# Sheet3.net
KiCad netlist of a schematic drawn in Altium Designer
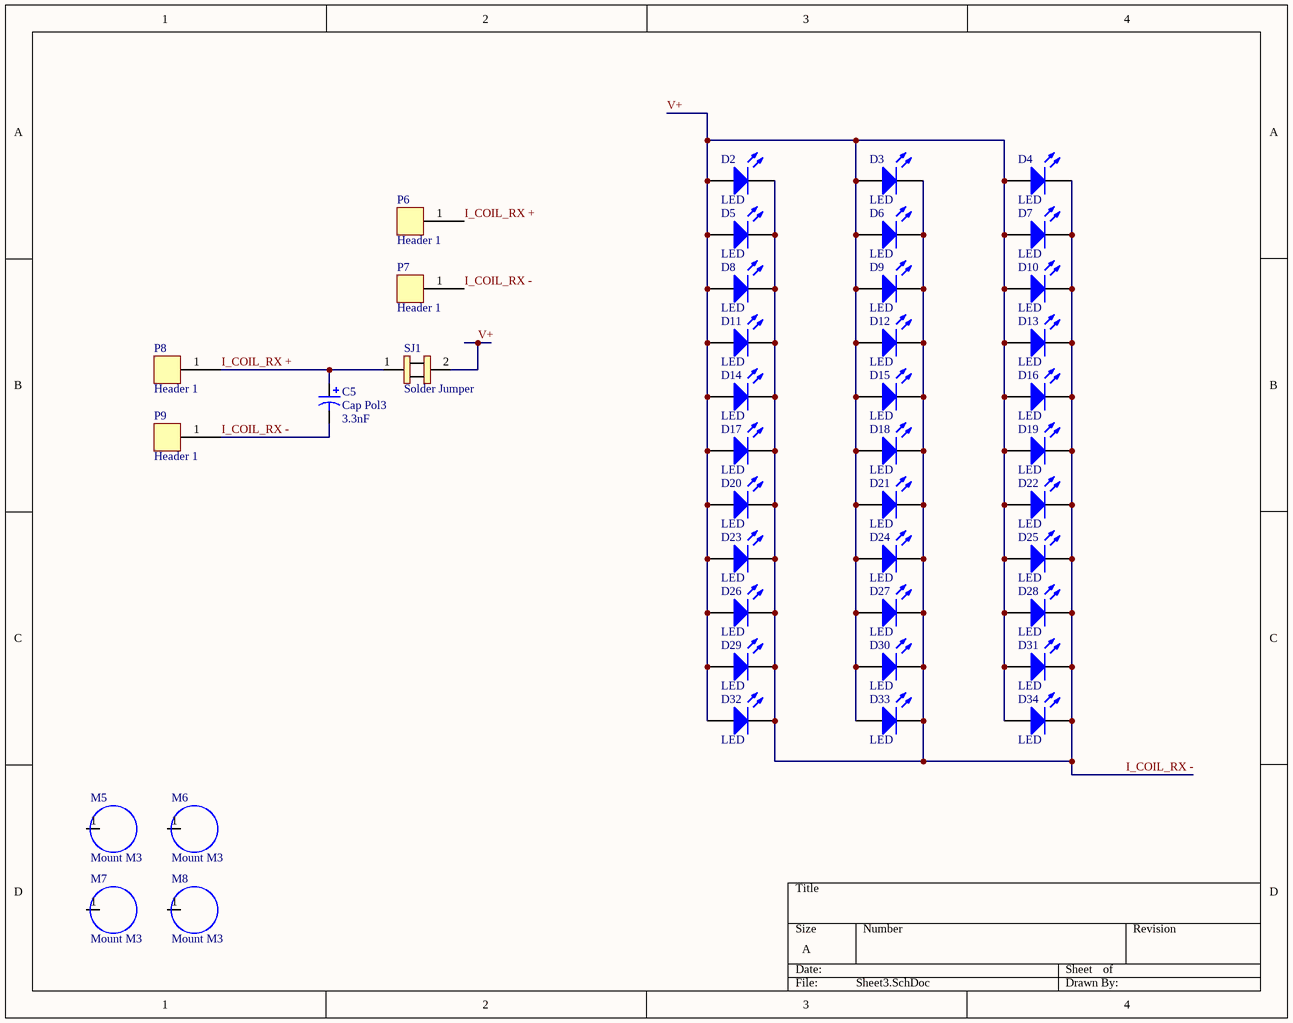
[diagram p0: Sheet3.SchDoc]

(export (version "E")
  (design (tool "Eeschema 10.0.6"))
  (components
    (comp (ref "C5")
      (value "Cap Pol3")
      (footprint "C0805")
      (description "Polarized Capacitor (Surface Mount)")
      (fields (field (name "ALTIUM_VALUE") "3.3nF") (field (name "PUBLISHER") "Altium Limited"))
      (libsource (lib "Miscellaneous Devices") (part "Cap Pol3"))
    )
    (comp (ref "D2")
      (value "LED")
      (footprint "0805")
      (description "Typical RED GaAs LED")
      (fields (field (name "PUBLISHER") "Altium Limited"))
      (libsource (lib "Miscellaneous Devices") (part "LED1"))
    )
    (comp (ref "D3")
      (value "LED")
      (footprint "0805")
      (description "Typical RED GaAs LED")
      (fields (field (name "PUBLISHER") "Altium Limited"))
      (libsource (lib "Miscellaneous Devices") (part "LED1"))
    )
    (comp (ref "D4")
      (value "LED")
      (footprint "0805")
      (description "Typical RED GaAs LED")
      (fields (field (name "PUBLISHER") "Altium Limited"))
      (libsource (lib "Miscellaneous Devices") (part "LED1"))
    )
    (comp (ref "D5")
      (value "LED")
      (footprint "0805")
      (description "Typical RED GaAs LED")
      (fields (field (name "PUBLISHER") "Altium Limited"))
      (libsource (lib "Miscellaneous Devices") (part "LED1"))
    )
    (comp (ref "D6")
      (value "LED")
      (footprint "0805")
      (description "Typical RED GaAs LED")
      (fields (field (name "PUBLISHER") "Altium Limited"))
      (libsource (lib "Miscellaneous Devices") (part "LED1"))
    )
    (comp (ref "D7")
      (value "LED")
      (footprint "0805")
      (description "Typical RED GaAs LED")
      (fields (field (name "PUBLISHER") "Altium Limited"))
      (libsource (lib "Miscellaneous Devices") (part "LED1"))
    )
    (comp (ref "D8")
      (value "LED")
      (footprint "0805")
      (description "Typical RED GaAs LED")
      (fields (field (name "PUBLISHER") "Altium Limited"))
      (libsource (lib "Miscellaneous Devices") (part "LED1"))
    )
    (comp (ref "D9")
      (value "LED")
      (footprint "0805")
      (description "Typical RED GaAs LED")
      (fields (field (name "PUBLISHER") "Altium Limited"))
      (libsource (lib "Miscellaneous Devices") (part "LED1"))
    )
    (comp (ref "D10")
      (value "LED")
      (footprint "0805")
      (description "Typical RED GaAs LED")
      (fields (field (name "PUBLISHER") "Altium Limited"))
      (libsource (lib "Miscellaneous Devices") (part "LED1"))
    )
    (comp (ref "D11")
      (value "LED")
      (footprint "0805")
      (description "Typical RED GaAs LED")
      (fields (field (name "PUBLISHER") "Altium Limited"))
      (libsource (lib "Miscellaneous Devices") (part "LED1"))
    )
    (comp (ref "D12")
      (value "LED")
      (footprint "0805")
      (description "Typical RED GaAs LED")
      (fields (field (name "PUBLISHER") "Altium Limited"))
      (libsource (lib "Miscellaneous Devices") (part "LED1"))
    )
    (comp (ref "D13")
      (value "LED")
      (footprint "0805")
      (description "Typical RED GaAs LED")
      (fields (field (name "PUBLISHER") "Altium Limited"))
      (libsource (lib "Miscellaneous Devices") (part "LED1"))
    )
    (comp (ref "D14")
      (value "LED")
      (footprint "0805")
      (description "Typical RED GaAs LED")
      (fields (field (name "PUBLISHER") "Altium Limited"))
      (libsource (lib "Miscellaneous Devices") (part "LED1"))
    )
    (comp (ref "D15")
      (value "LED")
      (footprint "0805")
      (description "Typical RED GaAs LED")
      (fields (field (name "PUBLISHER") "Altium Limited"))
      (libsource (lib "Miscellaneous Devices") (part "LED1"))
    )
    (comp (ref "D16")
      (value "LED")
      (footprint "0805")
      (description "Typical RED GaAs LED")
      (fields (field (name "PUBLISHER") "Altium Limited"))
      (libsource (lib "Miscellaneous Devices") (part "LED1"))
    )
    (comp (ref "D17")
      (value "LED")
      (footprint "0805")
      (description "Typical RED GaAs LED")
      (fields (field (name "PUBLISHER") "Altium Limited"))
      (libsource (lib "Miscellaneous Devices") (part "LED1"))
    )
    (comp (ref "D18")
      (value "LED")
      (footprint "0805")
      (description "Typical RED GaAs LED")
      (fields (field (name "PUBLISHER") "Altium Limited"))
      (libsource (lib "Miscellaneous Devices") (part "LED1"))
    )
    (comp (ref "D19")
      (value "LED")
      (footprint "0805")
      (description "Typical RED GaAs LED")
      (fields (field (name "PUBLISHER") "Altium Limited"))
      (libsource (lib "Miscellaneous Devices") (part "LED1"))
    )
    (comp (ref "D20")
      (value "LED")
      (footprint "0805")
      (description "Typical RED GaAs LED")
      (fields (field (name "PUBLISHER") "Altium Limited"))
      (libsource (lib "Miscellaneous Devices") (part "LED1"))
    )
    (comp (ref "D21")
      (value "LED")
      (footprint "0805")
      (description "Typical RED GaAs LED")
      (fields (field (name "PUBLISHER") "Altium Limited"))
      (libsource (lib "Miscellaneous Devices") (part "LED1"))
    )
    (comp (ref "D22")
      (value "LED")
      (footprint "0805")
      (description "Typical RED GaAs LED")
      (fields (field (name "PUBLISHER") "Altium Limited"))
      (libsource (lib "Miscellaneous Devices") (part "LED1"))
    )
    (comp (ref "D23")
      (value "LED")
      (footprint "0805")
      (description "Typical RED GaAs LED")
      (fields (field (name "PUBLISHER") "Altium Limited"))
      (libsource (lib "Miscellaneous Devices") (part "LED1"))
    )
    (comp (ref "D24")
      (value "LED")
      (footprint "0805")
      (description "Typical RED GaAs LED")
      (fields (field (name "PUBLISHER") "Altium Limited"))
      (libsource (lib "Miscellaneous Devices") (part "LED1"))
    )
    (comp (ref "D25")
      (value "LED")
      (footprint "0805")
      (description "Typical RED GaAs LED")
      (fields (field (name "PUBLISHER") "Altium Limited"))
      (libsource (lib "Miscellaneous Devices") (part "LED1"))
    )
    (comp (ref "D26")
      (value "LED")
      (footprint "0805")
      (description "Typical RED GaAs LED")
      (fields (field (name "PUBLISHER") "Altium Limited"))
      (libsource (lib "Miscellaneous Devices") (part "LED1"))
    )
    (comp (ref "D27")
      (value "LED")
      (footprint "0805")
      (description "Typical RED GaAs LED")
      (fields (field (name "PUBLISHER") "Altium Limited"))
      (libsource (lib "Miscellaneous Devices") (part "LED1"))
    )
    (comp (ref "D28")
      (value "LED")
      (footprint "0805")
      (description "Typical RED GaAs LED")
      (fields (field (name "PUBLISHER") "Altium Limited"))
      (libsource (lib "Miscellaneous Devices") (part "LED1"))
    )
    (comp (ref "D29")
      (value "LED")
      (footprint "0805")
      (description "Typical RED GaAs LED")
      (fields (field (name "PUBLISHER") "Altium Limited"))
      (libsource (lib "Miscellaneous Devices") (part "LED1"))
    )
    (comp (ref "D30")
      (value "LED")
      (footprint "0805")
      (description "Typical RED GaAs LED")
      (fields (field (name "PUBLISHER") "Altium Limited"))
      (libsource (lib "Miscellaneous Devices") (part "LED1"))
    )
    (comp (ref "D31")
      (value "LED")
      (footprint "0805")
      (description "Typical RED GaAs LED")
      (fields (field (name "PUBLISHER") "Altium Limited"))
      (libsource (lib "Miscellaneous Devices") (part "LED1"))
    )
    (comp (ref "D32")
      (value "LED")
      (footprint "0805")
      (description "Typical RED GaAs LED")
      (fields (field (name "PUBLISHER") "Altium Limited"))
      (libsource (lib "Miscellaneous Devices") (part "LED1"))
    )
    (comp (ref "D33")
      (value "LED")
      (footprint "0805")
      (description "Typical RED GaAs LED")
      (fields (field (name "PUBLISHER") "Altium Limited"))
      (libsource (lib "Miscellaneous Devices") (part "LED1"))
    )
    (comp (ref "D34")
      (value "LED")
      (footprint "0805")
      (description "Typical RED GaAs LED")
      (fields (field (name "PUBLISHER") "Altium Limited"))
      (libsource (lib "Miscellaneous Devices") (part "LED1"))
    )
    (comp (ref "M5") (value "Mount M3") (libsource (lib "u104Systems") (part "Mount M3")))
    (comp (ref "M6") (value "Mount M3") (libsource (lib "u104Systems") (part "Mount M3")))
    (comp (ref "M7") (value "Mount M3") (libsource (lib "u104Systems") (part "Mount M3")))
    (comp (ref "M8") (value "Mount M3") (libsource (lib "u104Systems") (part "Mount M3")))
    (comp (ref "P6") (value "Header 1") (footprint "Pad") (libsource (lib "u104Systems") (part "Header 1")))
    (comp (ref "P7") (value "Header 1") (footprint "Pad") (libsource (lib "u104Systems") (part "Header 1")))
    (comp (ref "P8") (value "Header 1") (footprint "Pad") (libsource (lib "u104Systems") (part "Header 1")))
    (comp (ref "P9") (value "Header 1") (footprint "Pad") (libsource (lib "u104Systems") (part "Header 1")))
    (comp (ref "SJ1") (value "Solder Jumper") (libsource (lib "u104Systems") (part "Solder Jumper")))
  )
  (nets
    (net (code "1") (name "/I_COIL_RX +") (class "Default")
      (node (ref "C5") (pin "1") (pinfunction "1_1") (pintype "passive"))
      (node (ref "P6") (pin "1") (pinfunction "1_1") (pintype "passive"))
      (node (ref "P8") (pin "1") (pinfunction "1_1") (pintype "passive"))
      (node (ref "SJ1") (pin "1") (pinfunction "1_1") (pintype "passive"))
    )
    (net (code "2") (name "/I_COIL_RX -") (class "Default")
      (node (ref "C5") (pin "2") (pinfunction "2_2") (pintype "passive"))
      (node (ref "D10") (pin "2") (pinfunction "K_2") (pintype "passive"))
      (node (ref "D11") (pin "2") (pinfunction "K_2") (pintype "passive"))
      (node (ref "D12") (pin "2") (pinfunction "K_2") (pintype "passive"))
      (node (ref "D13") (pin "2") (pinfunction "K_2") (pintype "passive"))
      (node (ref "D14") (pin "2") (pinfunction "K_2") (pintype "passive"))
      (node (ref "D15") (pin "2") (pinfunction "K_2") (pintype "passive"))
      (node (ref "D16") (pin "2") (pinfunction "K_2") (pintype "passive"))
      (node (ref "D17") (pin "2") (pinfunction "K_2") (pintype "passive"))
      (node (ref "D18") (pin "2") (pinfunction "K_2") (pintype "passive"))
      (node (ref "D19") (pin "2") (pinfunction "K_2") (pintype "passive"))
      (node (ref "D2") (pin "2") (pinfunction "K_2") (pintype "passive"))
      (node (ref "D20") (pin "2") (pinfunction "K_2") (pintype "passive"))
      (node (ref "D21") (pin "2") (pinfunction "K_2") (pintype "passive"))
      (node (ref "D22") (pin "2") (pinfunction "K_2") (pintype "passive"))
      (node (ref "D23") (pin "2") (pinfunction "K_2") (pintype "passive"))
      (node (ref "D24") (pin "2") (pinfunction "K_2") (pintype "passive"))
      (node (ref "D25") (pin "2") (pinfunction "K_2") (pintype "passive"))
      (node (ref "D26") (pin "2") (pinfunction "K_2") (pintype "passive"))
      (node (ref "D27") (pin "2") (pinfunction "K_2") (pintype "passive"))
      (node (ref "D28") (pin "2") (pinfunction "K_2") (pintype "passive"))
      (node (ref "D29") (pin "2") (pinfunction "K_2") (pintype "passive"))
      (node (ref "D3") (pin "2") (pinfunction "K_2") (pintype "passive"))
      (node (ref "D30") (pin "2") (pinfunction "K_2") (pintype "passive"))
      (node (ref "D31") (pin "2") (pinfunction "K_2") (pintype "passive"))
      (node (ref "D32") (pin "2") (pinfunction "K_2") (pintype "passive"))
      (node (ref "D33") (pin "2") (pinfunction "K_2") (pintype "passive"))
      (node (ref "D34") (pin "2") (pinfunction "K_2") (pintype "passive"))
      (node (ref "D4") (pin "2") (pinfunction "K_2") (pintype "passive"))
      (node (ref "D5") (pin "2") (pinfunction "K_2") (pintype "passive"))
      (node (ref "D6") (pin "2") (pinfunction "K_2") (pintype "passive"))
      (node (ref "D7") (pin "2") (pinfunction "K_2") (pintype "passive"))
      (node (ref "D8") (pin "2") (pinfunction "K_2") (pintype "passive"))
      (node (ref "D9") (pin "2") (pinfunction "K_2") (pintype "passive"))
      (node (ref "P7") (pin "1") (pinfunction "1_1") (pintype "passive"))
      (node (ref "P9") (pin "1") (pinfunction "1_1") (pintype "passive"))
    )
    (net (code "3") (name "/V+") (class "Default")
      (node (ref "D10") (pin "1") (pinfunction "A_1") (pintype "passive"))
      (node (ref "D11") (pin "1") (pinfunction "A_1") (pintype "passive"))
      (node (ref "D12") (pin "1") (pinfunction "A_1") (pintype "passive"))
      (node (ref "D13") (pin "1") (pinfunction "A_1") (pintype "passive"))
      (node (ref "D14") (pin "1") (pinfunction "A_1") (pintype "passive"))
      (node (ref "D15") (pin "1") (pinfunction "A_1") (pintype "passive"))
      (node (ref "D16") (pin "1") (pinfunction "A_1") (pintype "passive"))
      (node (ref "D17") (pin "1") (pinfunction "A_1") (pintype "passive"))
      (node (ref "D18") (pin "1") (pinfunction "A_1") (pintype "passive"))
      (node (ref "D19") (pin "1") (pinfunction "A_1") (pintype "passive"))
      (node (ref "D2") (pin "1") (pinfunction "A_1") (pintype "passive"))
      (node (ref "D20") (pin "1") (pinfunction "A_1") (pintype "passive"))
      (node (ref "D21") (pin "1") (pinfunction "A_1") (pintype "passive"))
      (node (ref "D22") (pin "1") (pinfunction "A_1") (pintype "passive"))
      (node (ref "D23") (pin "1") (pinfunction "A_1") (pintype "passive"))
      (node (ref "D24") (pin "1") (pinfunction "A_1") (pintype "passive"))
      (node (ref "D25") (pin "1") (pinfunction "A_1") (pintype "passive"))
      (node (ref "D26") (pin "1") (pinfunction "A_1") (pintype "passive"))
      (node (ref "D27") (pin "1") (pinfunction "A_1") (pintype "passive"))
      (node (ref "D28") (pin "1") (pinfunction "A_1") (pintype "passive"))
      (node (ref "D29") (pin "1") (pinfunction "A_1") (pintype "passive"))
      (node (ref "D3") (pin "1") (pinfunction "A_1") (pintype "passive"))
      (node (ref "D30") (pin "1") (pinfunction "A_1") (pintype "passive"))
      (node (ref "D31") (pin "1") (pinfunction "A_1") (pintype "passive"))
      (node (ref "D32") (pin "1") (pinfunction "A_1") (pintype "passive"))
      (node (ref "D33") (pin "1") (pinfunction "A_1") (pintype "passive"))
      (node (ref "D34") (pin "1") (pinfunction "A_1") (pintype "passive"))
      (node (ref "D4") (pin "1") (pinfunction "A_1") (pintype "passive"))
      (node (ref "D5") (pin "1") (pinfunction "A_1") (pintype "passive"))
      (node (ref "D6") (pin "1") (pinfunction "A_1") (pintype "passive"))
      (node (ref "D7") (pin "1") (pinfunction "A_1") (pintype "passive"))
      (node (ref "D8") (pin "1") (pinfunction "A_1") (pintype "passive"))
      (node (ref "D9") (pin "1") (pinfunction "A_1") (pintype "passive"))
      (node (ref "SJ1") (pin "2") (pinfunction "2_2") (pintype "passive"))
    )
    (net (code "4") (name "unconnected-(M5-Pad1)") (class "Default")
      (node (ref "M5") (pin "1") (pinfunction "1_1") (pintype "passive"))
    )
    (net (code "5") (name "unconnected-(M6-Pad1)") (class "Default")
      (node (ref "M6") (pin "1") (pinfunction "1_1") (pintype "passive"))
    )
    (net (code "6") (name "unconnected-(M7-Pad1)") (class "Default")
      (node (ref "M7") (pin "1") (pinfunction "1_1") (pintype "passive"))
    )
    (net (code "7") (name "unconnected-(M8-Pad1)") (class "Default")
      (node (ref "M8") (pin "1") (pinfunction "1_1") (pintype "passive"))
    )
  )
)
